# bubbledisplaybackpack_v01.net
KiCad netlist of a schematic drawn in EAGLE
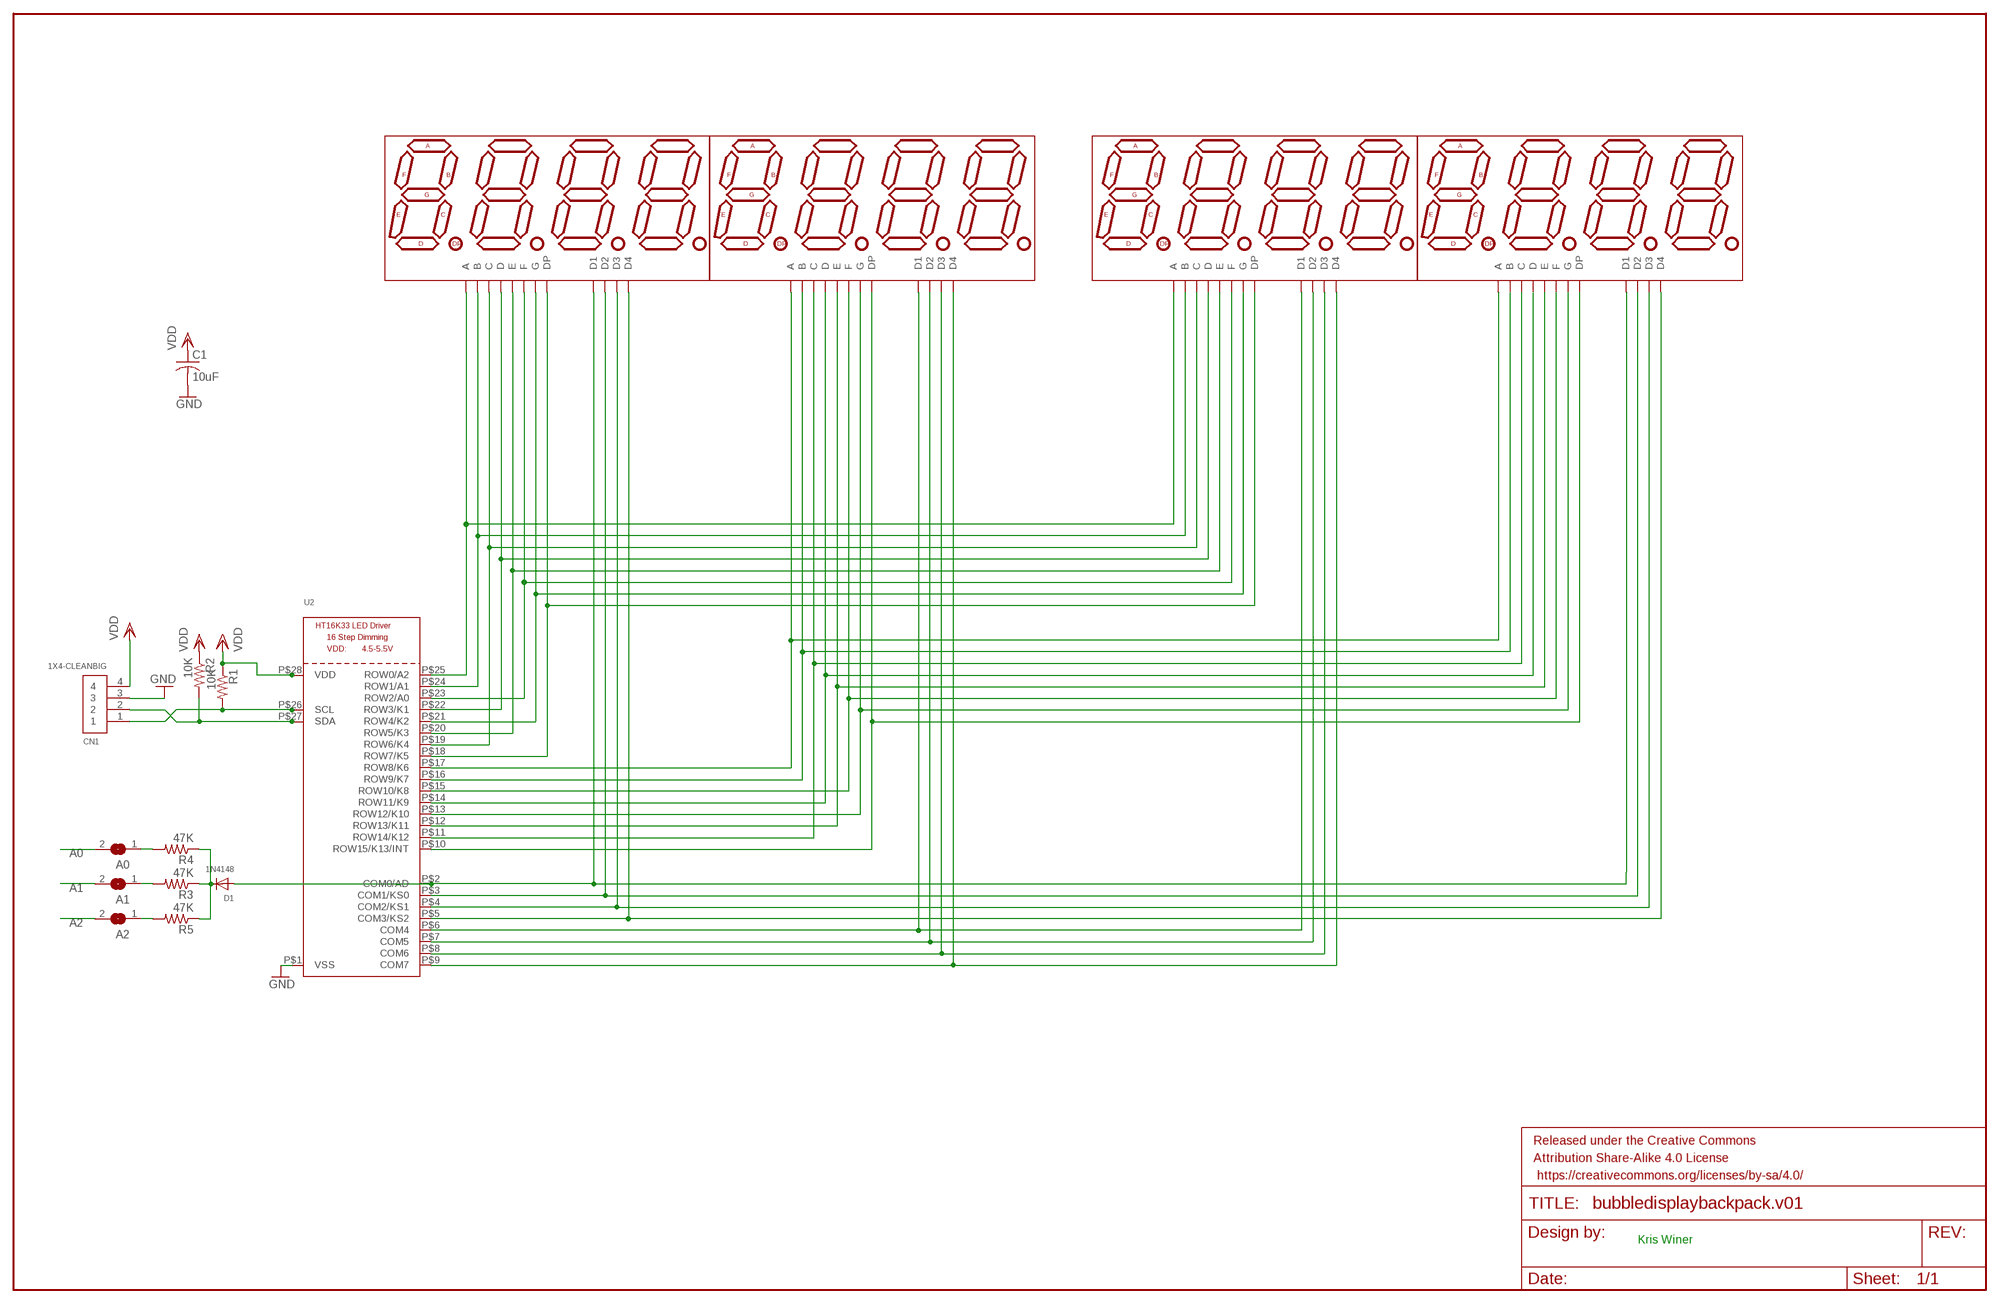
[diagram p0: schematic, sheet 1]

(export (version "E")
  (design (tool "Eeschema 10.0.6"))
  (components
    (comp (ref "A0")
      (value "SOLDERJUMPERREFLOW_NOPASTE")
      (footprint "eagle-import:SOLDERJUMPER_REFLOW_NOPASTE")
      (libsource (lib "eagle-import") (part "SOLDERJUMPERREFLOW_NOPASTE"))
    )
    (comp (ref "A1")
      (value "SOLDERJUMPERREFLOW_NOPASTE")
      (footprint "eagle-import:SOLDERJUMPER_REFLOW_NOPASTE")
      (libsource (lib "eagle-import") (part "SOLDERJUMPERREFLOW_NOPASTE"))
    )
    (comp (ref "A2")
      (value "SOLDERJUMPERREFLOW_NOPASTE")
      (footprint "eagle-import:SOLDERJUMPER_REFLOW_NOPASTE")
      (libsource (lib "eagle-import") (part "SOLDERJUMPERREFLOW_NOPASTE"))
    )
    (comp (ref "C1")
      (value "10uF")
      (footprint "eagle-import:C0805K")
      (libsource (lib "eagle-import") (part "C-USC0805K"))
    )
    (comp (ref "CN1")
      (value "1X4-CLEANBIG")
      (footprint "eagle-import:1X04-CLEANBIG")
      (libsource (lib "eagle-import") (part "1X4-CLEANBIG"))
    )
    (comp (ref "D1")
      (value "1N4148")
      (footprint "eagle-import:SOD-323F")
      (libsource (lib "eagle-import") (part "DIODESOD-323F"))
    )
    (comp (ref "DISPLAY1")
      (value "hp")
      (footprint "eagle-import:DIL12")
      (libsource (lib "eagle-import") (part "7-SEGMENT-4DIGIT-COUNTER-HP-BUBBLE"))
    )
    (comp (ref "DISPLAY2")
      (value "hp")
      (footprint "eagle-import:DIL12")
      (libsource (lib "eagle-import") (part "7-SEGMENT-4DIGIT-COUNTER-HP-BUBBLE"))
    )
    (comp (ref "DISPLAY3")
      (value "hp")
      (footprint "eagle-import:DIL12")
      (libsource (lib "eagle-import") (part "7-SEGMENT-4DIGIT-COUNTER-HP-BUBBLE"))
    )
    (comp (ref "DISPLAY4")
      (value "hp")
      (footprint "eagle-import:DIL12")
      (libsource (lib "eagle-import") (part "7-SEGMENT-4DIGIT-COUNTER-HP-BUBBLE"))
    )
    (comp (ref "FRAME1")
      (value "FRAME-LEDGER")
      (footprint "eagle-import:CREATIVE_COMMONS")
      (libsource (lib "eagle-import") (part "FRAME-LEDGER"))
    )
    (comp (ref "R1")
      (value "10K")
      (footprint "eagle-import:R0805")
      (libsource (lib "eagle-import") (part "R-US_R0805"))
    )
    (comp (ref "R2")
      (value "10K")
      (footprint "eagle-import:R0805")
      (libsource (lib "eagle-import") (part "R-US_R0805"))
    )
    (comp (ref "R3")
      (value "47K")
      (footprint "eagle-import:R0805")
      (libsource (lib "eagle-import") (part "R-US_R0805"))
    )
    (comp (ref "R4")
      (value "47K")
      (footprint "eagle-import:R0805")
      (libsource (lib "eagle-import") (part "R-US_R0805"))
    )
    (comp (ref "R5")
      (value "47K")
      (footprint "eagle-import:R0805")
      (libsource (lib "eagle-import") (part "R-US_R0805"))
    )
    (comp (ref "U2")
      (value "HT16K33_SOP28")
      (footprint "eagle-import:SOP28_300MIL")
      (libsource (lib "eagle-import") (part "HT16K33_SOP28"))
    )
  )
  (nets
    (net (code "1") (name "/A0") (class "Default")
      (node (ref "A0") (pin "2") (pinfunction "2_2") (pintype "passive"))
      (node (ref "DISPLAY1") (pin "9") (pinfunction "F_9") (pintype "bidirectional"))
      (node (ref "DISPLAY3") (pin "9") (pinfunction "F_9") (pintype "bidirectional"))
      (node (ref "U2") (pin "P$23") (pinfunction "ROW2/A0_P$23") (pintype "bidirectional"))
    )
    (net (code "2") (name "/A1") (class "Default")
      (node (ref "A1") (pin "2") (pinfunction "2_2") (pintype "passive"))
      (node (ref "DISPLAY1") (pin "11") (pinfunction "B_11") (pintype "bidirectional"))
      (node (ref "DISPLAY3") (pin "11") (pinfunction "B_11") (pintype "bidirectional"))
      (node (ref "U2") (pin "P$24") (pinfunction "ROW1/A1_P$24") (pintype "bidirectional"))
    )
    (net (code "3") (name "/A2") (class "Default")
      (node (ref "A2") (pin "2") (pinfunction "2_2") (pintype "passive"))
      (node (ref "DISPLAY1") (pin "12") (pinfunction "A_12") (pintype "bidirectional"))
      (node (ref "DISPLAY3") (pin "12") (pinfunction "A_12") (pintype "bidirectional"))
      (node (ref "U2") (pin "P$25") (pinfunction "ROW0/A2_P$25") (pintype "bidirectional"))
    )
    (net (code "4") (name "GND") (class "Default")
      (node (ref "C1") (pin "2") (pinfunction "2_2") (pintype "passive"))
      (node (ref "CN1") (pin "3") (pinfunction "3_3") (pintype "bidirectional"))
      (node (ref "U2") (pin "P$1") (pinfunction "VSS_P$1") (pintype "bidirectional"))
    )
    (net (code "5") (name "Net-(A0-Pad1)") (class "Default")
      (node (ref "A0") (pin "1") (pinfunction "1_1") (pintype "passive"))
      (node (ref "R4") (pin "2") (pinfunction "2_2") (pintype "passive"))
    )
    (net (code "6") (name "Net-(A1-Pad1)") (class "Default")
      (node (ref "A1") (pin "1") (pinfunction "1_1") (pintype "passive"))
      (node (ref "R3") (pin "2") (pinfunction "2_2") (pintype "passive"))
    )
    (net (code "7") (name "Net-(A2-Pad1)") (class "Default")
      (node (ref "A2") (pin "1") (pinfunction "1_1") (pintype "passive"))
      (node (ref "R5") (pin "2") (pinfunction "2_2") (pintype "passive"))
    )
    (net (code "8") (name "Net-(D1-PadC)") (class "Default")
      (node (ref "D1") (pin "C") (pinfunction "C_C") (pintype "passive"))
      (node (ref "R3") (pin "1") (pinfunction "1_1") (pintype "passive"))
      (node (ref "R4") (pin "1") (pinfunction "1_1") (pintype "passive"))
      (node (ref "R5") (pin "1") (pinfunction "1_1") (pintype "passive"))
    )
    (net (code "9") (name "Net-(DISPLAY1-C)") (class "Default")
      (node (ref "DISPLAY1") (pin "3") (pinfunction "C_3") (pintype "bidirectional"))
      (node (ref "DISPLAY3") (pin "3") (pinfunction "C_3") (pintype "bidirectional"))
      (node (ref "U2") (pin "P$19") (pinfunction "ROW6/K4_P$19") (pintype "bidirectional"))
    )
    (net (code "10") (name "Net-(DISPLAY1-D)") (class "Default")
      (node (ref "DISPLAY1") (pin "8") (pinfunction "D_8") (pintype "bidirectional"))
      (node (ref "DISPLAY3") (pin "8") (pinfunction "D_8") (pintype "bidirectional"))
      (node (ref "U2") (pin "P$22") (pinfunction "ROW3/K1_P$22") (pintype "bidirectional"))
    )
    (net (code "11") (name "Net-(DISPLAY1-D1)") (class "Default")
      (node (ref "DISPLAY1") (pin "1") (pinfunction "D1_1") (pintype "bidirectional"))
      (node (ref "DISPLAY4") (pin "1") (pinfunction "D1_1") (pintype "bidirectional"))
      (node (ref "U2") (pin "P$6") (pinfunction "COM4_P$6") (pintype "bidirectional"))
    )
    (net (code "12") (name "Net-(DISPLAY1-D2)") (class "Default")
      (node (ref "DISPLAY1") (pin "10") (pinfunction "D2_10") (pintype "bidirectional"))
      (node (ref "DISPLAY4") (pin "10") (pinfunction "D2_10") (pintype "bidirectional"))
      (node (ref "U2") (pin "P$7") (pinfunction "COM5_P$7") (pintype "bidirectional"))
    )
    (net (code "13") (name "Net-(DISPLAY1-D3)") (class "Default")
      (node (ref "DISPLAY1") (pin "4") (pinfunction "D3_4") (pintype "bidirectional"))
      (node (ref "DISPLAY4") (pin "4") (pinfunction "D3_4") (pintype "bidirectional"))
      (node (ref "U2") (pin "P$8") (pinfunction "COM6_P$8") (pintype "bidirectional"))
    )
    (net (code "14") (name "Net-(DISPLAY1-D4)") (class "Default")
      (node (ref "DISPLAY1") (pin "6") (pinfunction "D4_6") (pintype "bidirectional"))
      (node (ref "DISPLAY4") (pin "6") (pinfunction "D4_6") (pintype "bidirectional"))
      (node (ref "U2") (pin "P$9") (pinfunction "COM7_P$9") (pintype "bidirectional"))
    )
    (net (code "15") (name "Net-(DISPLAY1-DP)") (class "Default")
      (node (ref "DISPLAY1") (pin "5") (pinfunction "DP_5") (pintype "bidirectional"))
      (node (ref "DISPLAY3") (pin "5") (pinfunction "DP_5") (pintype "bidirectional"))
      (node (ref "U2") (pin "P$18") (pinfunction "ROW7/K5_P$18") (pintype "bidirectional"))
    )
    (net (code "16") (name "Net-(DISPLAY1-E)") (class "Default")
      (node (ref "DISPLAY1") (pin "2") (pinfunction "E_2") (pintype "bidirectional"))
      (node (ref "DISPLAY3") (pin "2") (pinfunction "E_2") (pintype "bidirectional"))
      (node (ref "U2") (pin "P$20") (pinfunction "ROW5/K3_P$20") (pintype "bidirectional"))
    )
    (net (code "17") (name "Net-(DISPLAY1-G)") (class "Default")
      (node (ref "DISPLAY1") (pin "7") (pinfunction "G_7") (pintype "bidirectional"))
      (node (ref "DISPLAY3") (pin "7") (pinfunction "G_7") (pintype "bidirectional"))
      (node (ref "U2") (pin "P$21") (pinfunction "ROW4/K2_P$21") (pintype "bidirectional"))
    )
    (net (code "18") (name "Net-(DISPLAY2-A)") (class "Default")
      (node (ref "DISPLAY2") (pin "12") (pinfunction "A_12") (pintype "bidirectional"))
      (node (ref "DISPLAY4") (pin "12") (pinfunction "A_12") (pintype "bidirectional"))
      (node (ref "U2") (pin "P$17") (pinfunction "ROW8/K6_P$17") (pintype "bidirectional"))
    )
    (net (code "19") (name "Net-(DISPLAY2-B)") (class "Default")
      (node (ref "DISPLAY2") (pin "11") (pinfunction "B_11") (pintype "bidirectional"))
      (node (ref "DISPLAY4") (pin "11") (pinfunction "B_11") (pintype "bidirectional"))
      (node (ref "U2") (pin "P$16") (pinfunction "ROW9/K7_P$16") (pintype "bidirectional"))
    )
    (net (code "20") (name "Net-(DISPLAY2-C)") (class "Default")
      (node (ref "DISPLAY2") (pin "3") (pinfunction "C_3") (pintype "bidirectional"))
      (node (ref "DISPLAY4") (pin "3") (pinfunction "C_3") (pintype "bidirectional"))
      (node (ref "U2") (pin "P$11") (pinfunction "ROW14/K12_P$11") (pintype "bidirectional"))
    )
    (net (code "21") (name "Net-(DISPLAY2-D)") (class "Default")
      (node (ref "DISPLAY2") (pin "8") (pinfunction "D_8") (pintype "bidirectional"))
      (node (ref "DISPLAY4") (pin "8") (pinfunction "D_8") (pintype "bidirectional"))
      (node (ref "U2") (pin "P$14") (pinfunction "ROW11/K9_P$14") (pintype "bidirectional"))
    )
    (net (code "22") (name "Net-(DISPLAY2-D1)") (class "Default")
      (node (ref "D1") (pin "A") (pinfunction "A_A") (pintype "passive"))
      (node (ref "DISPLAY2") (pin "1") (pinfunction "D1_1") (pintype "bidirectional"))
      (node (ref "DISPLAY3") (pin "1") (pinfunction "D1_1") (pintype "bidirectional"))
      (node (ref "U2") (pin "P$2") (pinfunction "COM0/AD_P$2") (pintype "bidirectional"))
    )
    (net (code "23") (name "Net-(DISPLAY2-D2)") (class "Default")
      (node (ref "DISPLAY2") (pin "10") (pinfunction "D2_10") (pintype "bidirectional"))
      (node (ref "DISPLAY3") (pin "10") (pinfunction "D2_10") (pintype "bidirectional"))
      (node (ref "U2") (pin "P$3") (pinfunction "COM1/KS0_P$3") (pintype "bidirectional"))
    )
    (net (code "24") (name "Net-(DISPLAY2-D3)") (class "Default")
      (node (ref "DISPLAY2") (pin "4") (pinfunction "D3_4") (pintype "bidirectional"))
      (node (ref "DISPLAY3") (pin "4") (pinfunction "D3_4") (pintype "bidirectional"))
      (node (ref "U2") (pin "P$4") (pinfunction "COM2/KS1_P$4") (pintype "bidirectional"))
    )
    (net (code "25") (name "Net-(DISPLAY2-D4)") (class "Default")
      (node (ref "DISPLAY2") (pin "6") (pinfunction "D4_6") (pintype "bidirectional"))
      (node (ref "DISPLAY3") (pin "6") (pinfunction "D4_6") (pintype "bidirectional"))
      (node (ref "U2") (pin "P$5") (pinfunction "COM3/KS2_P$5") (pintype "bidirectional"))
    )
    (net (code "26") (name "Net-(DISPLAY2-DP)") (class "Default")
      (node (ref "DISPLAY2") (pin "5") (pinfunction "DP_5") (pintype "bidirectional"))
      (node (ref "DISPLAY4") (pin "5") (pinfunction "DP_5") (pintype "bidirectional"))
      (node (ref "U2") (pin "P$10") (pinfunction "ROW15/K13/INT_P$10") (pintype "bidirectional"))
    )
    (net (code "27") (name "Net-(DISPLAY2-E)") (class "Default")
      (node (ref "DISPLAY2") (pin "2") (pinfunction "E_2") (pintype "bidirectional"))
      (node (ref "DISPLAY4") (pin "2") (pinfunction "E_2") (pintype "bidirectional"))
      (node (ref "U2") (pin "P$12") (pinfunction "ROW13/K11_P$12") (pintype "bidirectional"))
    )
    (net (code "28") (name "Net-(DISPLAY2-F)") (class "Default")
      (node (ref "DISPLAY2") (pin "9") (pinfunction "F_9") (pintype "bidirectional"))
      (node (ref "DISPLAY4") (pin "9") (pinfunction "F_9") (pintype "bidirectional"))
      (node (ref "U2") (pin "P$15") (pinfunction "ROW10/K8_P$15") (pintype "bidirectional"))
    )
    (net (code "29") (name "Net-(DISPLAY2-G)") (class "Default")
      (node (ref "DISPLAY2") (pin "7") (pinfunction "G_7") (pintype "bidirectional"))
      (node (ref "DISPLAY4") (pin "7") (pinfunction "G_7") (pintype "bidirectional"))
      (node (ref "U2") (pin "P$13") (pinfunction "ROW12/K10_P$13") (pintype "bidirectional"))
    )
    (net (code "30") (name "Net-(U2-SCL)") (class "Default")
      (node (ref "CN1") (pin "1") (pinfunction "1_1") (pintype "bidirectional"))
      (node (ref "R1") (pin "2") (pinfunction "2_2") (pintype "passive"))
      (node (ref "U2") (pin "P$26") (pinfunction "SCL_P$26") (pintype "bidirectional"))
    )
    (net (code "31") (name "Net-(U2-SDA)") (class "Default")
      (node (ref "CN1") (pin "2") (pinfunction "2_2") (pintype "bidirectional"))
      (node (ref "R2") (pin "2") (pinfunction "2_2") (pintype "passive"))
      (node (ref "U2") (pin "P$27") (pinfunction "SDA_P$27") (pintype "bidirectional"))
    )
    (net (code "32") (name "VDD") (class "Default")
      (node (ref "C1") (pin "1") (pinfunction "1_1") (pintype "passive"))
      (node (ref "CN1") (pin "4") (pinfunction "4_4") (pintype "bidirectional"))
      (node (ref "R1") (pin "1") (pinfunction "1_1") (pintype "passive"))
      (node (ref "R2") (pin "1") (pinfunction "1_1") (pintype "passive"))
      (node (ref "U2") (pin "P$28") (pinfunction "VDD_P$28") (pintype "bidirectional"))
    )
  )
)
